# i2c_kbd6.net
KiCad netlist of a schematic drawn in EAGLE
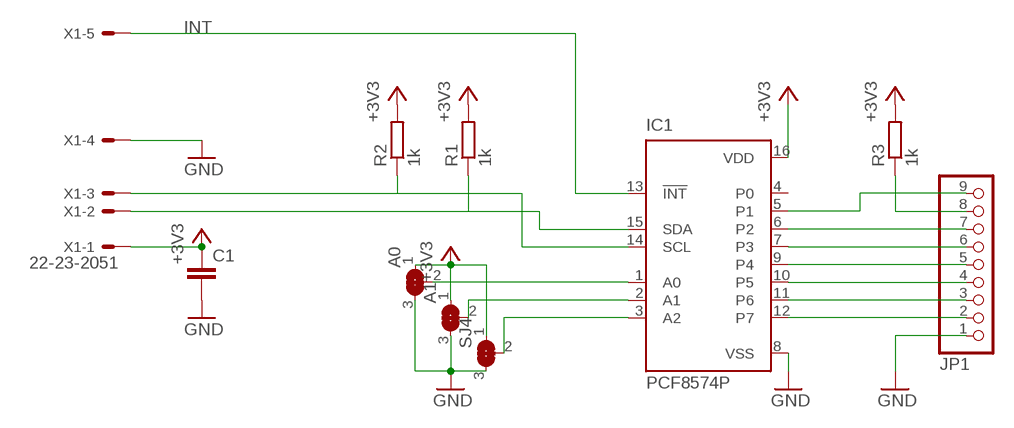
[diagram p0: schematic, sheet 1]

(export (version "E")
  (design (tool "Eeschema 10.0.6"))
  (components
    (comp (ref "A0")
      (value "SOLDERJUMPER_2WAY0805")
      (footprint "eagle-import:SOLDERJUMPER_2WAY_OPEN_0805")
      (libsource (lib "eagle-import") (part "SOLDERJUMPER_2WAY0805"))
    )
    (comp (ref "A1")
      (value "SOLDERJUMPER_2WAY0805")
      (footprint "eagle-import:SOLDERJUMPER_2WAY_OPEN_0805")
      (libsource (lib "eagle-import") (part "SOLDERJUMPER_2WAY0805"))
    )
    (comp (ref "C1")
      (value "C-EUC0805")
      (footprint "eagle-import:C0805")
      (libsource (lib "eagle-import") (part "C-EUC0805"))
    )
    (comp (ref "IC1")
      (value "PCF8574P")
      (footprint "eagle-import:DIL16")
      (fields (field (name "MPN") "PCF8574PN"))
      (libsource (lib "eagle-import") (part "PCF8574P"))
    )
    (comp (ref "JP1")
      (value "PINHD-1X9/90")
      (footprint "eagle-import:1X09_90")
      (libsource (lib "eagle-import") (part "PINHD-1X9/90"))
    )
    (comp (ref "R1")
      (value "1k")
      (footprint "eagle-import:R0805")
      (libsource (lib "eagle-import") (part "R-EU_R0805"))
    )
    (comp (ref "R2")
      (value "1k")
      (footprint "eagle-import:R0805")
      (libsource (lib "eagle-import") (part "R-EU_R0805"))
    )
    (comp (ref "R3")
      (value "1k")
      (footprint "eagle-import:R0805")
      (libsource (lib "eagle-import") (part "R-EU_R0805"))
    )
    (comp (ref "SJ4")
      (value "SOLDERJUMPER_2WAY0805")
      (footprint "eagle-import:SOLDERJUMPER_2WAY_OPEN_0805")
      (libsource (lib "eagle-import") (part "SOLDERJUMPER_2WAY0805"))
    )
    (comp (ref "X1")
      (value "22-23-2051")
      (footprint "eagle-import:22-23-2051")
      (fields (field (name "MF") "MOLEX"))
      (libsource (lib "eagle-import") (part "22-23-2051"))
    )
  )
  (nets
    (net (code "1") (name "+3V3") (class "Default")
      (node (ref "A0") (pin "1") (pinfunction "1_1") (pintype "passive"))
      (node (ref "A1") (pin "1") (pinfunction "1_1") (pintype "passive"))
      (node (ref "C1") (pin "1") (pinfunction "1_1") (pintype "passive"))
      (node (ref "IC1") (pin "16") (pinfunction "VDD_16") (pintype "power_in"))
      (node (ref "R1") (pin "2") (pinfunction "2_2") (pintype "passive"))
      (node (ref "R2") (pin "2") (pinfunction "2_2") (pintype "passive"))
      (node (ref "R3") (pin "2") (pinfunction "2_2") (pintype "passive"))
      (node (ref "SJ4") (pin "1") (pinfunction "1_1") (pintype "passive"))
      (node (ref "X1") (pin "1") (pinfunction "S_1") (pintype "passive"))
    )
    (net (code "2") (name "/INT") (class "Default")
      (node (ref "IC1") (pin "13") (pinfunction "~{INT}_13") (pintype "output"))
      (node (ref "X1") (pin "5") (pinfunction "S_5") (pintype "passive"))
    )
    (net (code "3") (name "GND") (class "Default")
      (node (ref "A0") (pin "3") (pinfunction "3_3") (pintype "passive"))
      (node (ref "A1") (pin "3") (pinfunction "3_3") (pintype "passive"))
      (node (ref "C1") (pin "2") (pinfunction "2_2") (pintype "passive"))
      (node (ref "IC1") (pin "8") (pinfunction "VSS_8") (pintype "power_in"))
      (node (ref "JP1") (pin "1") (pinfunction "1_1") (pintype "passive"))
      (node (ref "SJ4") (pin "3") (pinfunction "3_3") (pintype "passive"))
      (node (ref "X1") (pin "4") (pinfunction "S_4") (pintype "passive"))
    )
    (net (code "4") (name "Net-(IC1-A0)") (class "Default")
      (node (ref "A0") (pin "2") (pinfunction "2_2") (pintype "passive"))
      (node (ref "IC1") (pin "1") (pinfunction "A0_1") (pintype "input"))
    )
    (net (code "5") (name "Net-(IC1-A1)") (class "Default")
      (node (ref "A1") (pin "2") (pinfunction "2_2") (pintype "passive"))
      (node (ref "IC1") (pin "2") (pinfunction "A1_2") (pintype "input"))
    )
    (net (code "6") (name "Net-(IC1-A2)") (class "Default")
      (node (ref "IC1") (pin "3") (pinfunction "A2_3") (pintype "input"))
      (node (ref "SJ4") (pin "2") (pinfunction "2_2") (pintype "passive"))
    )
    (net (code "7") (name "Net-(IC1-P1)") (class "Default")
      (node (ref "IC1") (pin "5") (pinfunction "P1_5") (pintype "bidirectional"))
      (node (ref "JP1") (pin "9") (pinfunction "9_9") (pintype "passive"))
    )
    (net (code "8") (name "Net-(IC1-P2)") (class "Default")
      (node (ref "IC1") (pin "6") (pinfunction "P2_6") (pintype "bidirectional"))
      (node (ref "JP1") (pin "7") (pinfunction "7_7") (pintype "passive"))
    )
    (net (code "9") (name "Net-(IC1-P3)") (class "Default")
      (node (ref "IC1") (pin "7") (pinfunction "P3_7") (pintype "bidirectional"))
      (node (ref "JP1") (pin "6") (pinfunction "6_6") (pintype "passive"))
    )
    (net (code "10") (name "Net-(IC1-P4)") (class "Default")
      (node (ref "IC1") (pin "9") (pinfunction "P4_9") (pintype "bidirectional"))
      (node (ref "JP1") (pin "5") (pinfunction "5_5") (pintype "passive"))
    )
    (net (code "11") (name "Net-(IC1-P5)") (class "Default")
      (node (ref "IC1") (pin "10") (pinfunction "P5_10") (pintype "bidirectional"))
      (node (ref "JP1") (pin "4") (pinfunction "4_4") (pintype "passive"))
    )
    (net (code "12") (name "Net-(IC1-P6)") (class "Default")
      (node (ref "IC1") (pin "11") (pinfunction "P6_11") (pintype "bidirectional"))
      (node (ref "JP1") (pin "3") (pinfunction "3_3") (pintype "passive"))
    )
    (net (code "13") (name "Net-(IC1-P7)") (class "Default")
      (node (ref "IC1") (pin "12") (pinfunction "P7_12") (pintype "bidirectional"))
      (node (ref "JP1") (pin "2") (pinfunction "2_2") (pintype "passive"))
    )
    (net (code "14") (name "Net-(IC1-SCL)") (class "Default")
      (node (ref "IC1") (pin "14") (pinfunction "SCL_14") (pintype "input"))
      (node (ref "R2") (pin "1") (pinfunction "1_1") (pintype "passive"))
      (node (ref "X1") (pin "3") (pinfunction "S_3") (pintype "passive"))
    )
    (net (code "15") (name "Net-(IC1-SDA)") (class "Default")
      (node (ref "IC1") (pin "15") (pinfunction "SDA_15") (pintype "bidirectional"))
      (node (ref "R1") (pin "1") (pinfunction "1_1") (pintype "passive"))
      (node (ref "X1") (pin "2") (pinfunction "S_2") (pintype "passive"))
    )
    (net (code "16") (name "Net-(JP1-Pad8)") (class "Default")
      (node (ref "JP1") (pin "8") (pinfunction "8_8") (pintype "passive"))
      (node (ref "R3") (pin "1") (pinfunction "1_1") (pintype "passive"))
    )
    (net (code "17") (name "unconnected-(IC1-P0-Pad4)") (class "Default")
      (node (ref "IC1") (pin "4") (pinfunction "P0_4") (pintype "bidirectional"))
    )
  )
)
